# clock.net
KiCad netlist of a schematic drawn in EAGLE
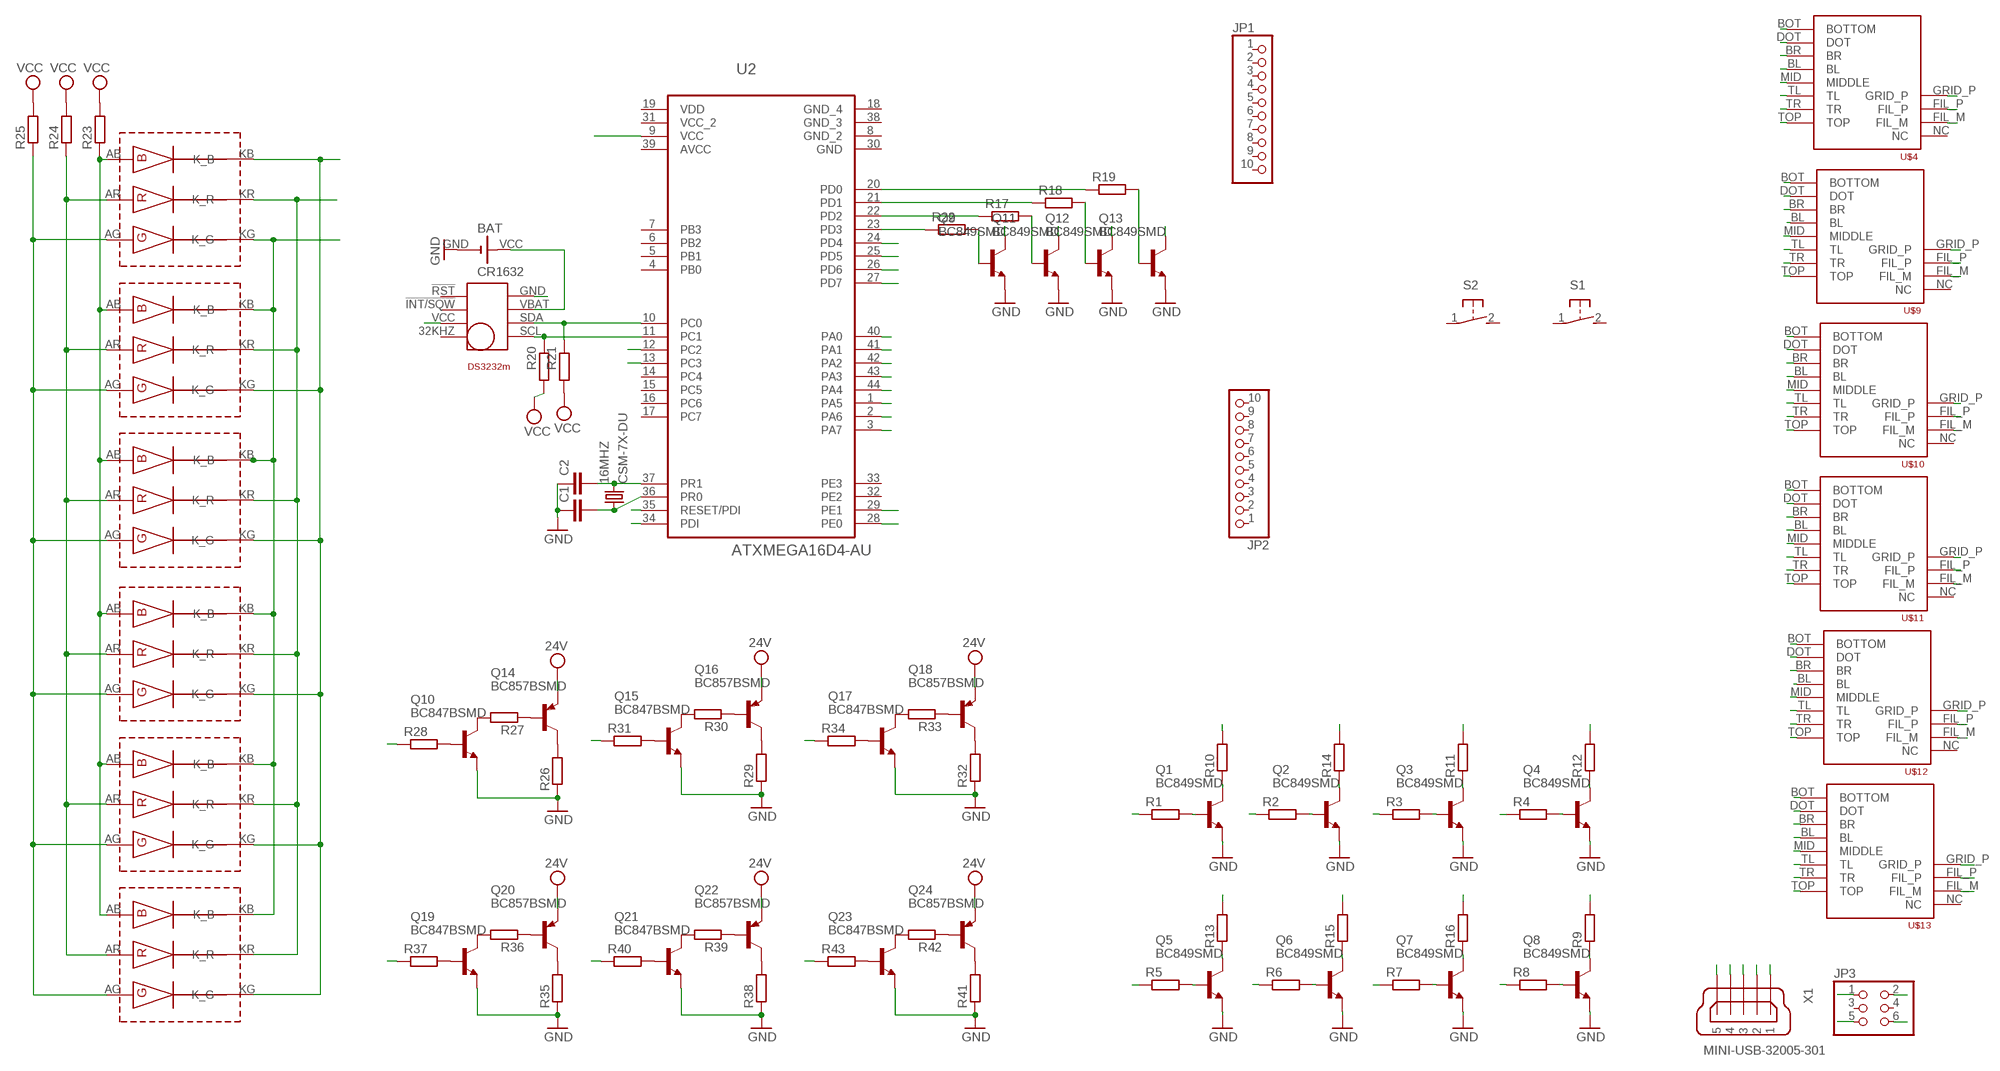
[diagram p0: schematic, sheet 1]

(export (version "E")
  (design (tool "Eeschema 10.0.6"))
  (components
    (comp (ref "16MHZ")
      (value "CSM-7X-DU")
      (footprint "eagle-import:CSM-7X-DU")
      (libsource (lib "eagle-import") (part "CSM-7X-DU"))
    )
    (comp (ref "BAT")
      (value "CR1632")
      (footprint "eagle-import:CR3232")
      (libsource (lib "eagle-import") (part "CR1632"))
    )
    (comp (ref "C1")
      (value "C-EUC0805K")
      (footprint "eagle-import:C0805K")
      (libsource (lib "eagle-import") (part "C-EUC0805K"))
    )
    (comp (ref "C2")
      (value "C-EUC0805K")
      (footprint "eagle-import:C0805K")
      (libsource (lib "eagle-import") (part "C-EUC0805K"))
    )
    (comp (ref "JP1")
      (value "PINHD-1X10")
      (footprint "eagle-import:1X10")
      (libsource (lib "eagle-import") (part "PINHD-1X10"))
    )
    (comp (ref "JP2")
      (value "PINHD-1X10")
      (footprint "eagle-import:1X10")
      (libsource (lib "eagle-import") (part "PINHD-1X10"))
    )
    (comp (ref "JP3")
      (value "PINHD-2X3/90")
      (footprint "eagle-import:2X03_90")
      (libsource (lib "eagle-import") (part "PINHD-2X3/90"))
    )
    (comp (ref "Q1")
      (value "BC849SMD")
      (footprint "eagle-import:SOT23-BEC")
      (libsource (lib "eagle-import") (part "BC849SMD"))
    )
    (comp (ref "Q2")
      (value "BC849SMD")
      (footprint "eagle-import:SOT23-BEC")
      (libsource (lib "eagle-import") (part "BC849SMD"))
    )
    (comp (ref "Q3")
      (value "BC849SMD")
      (footprint "eagle-import:SOT23-BEC")
      (libsource (lib "eagle-import") (part "BC849SMD"))
    )
    (comp (ref "Q4")
      (value "BC849SMD")
      (footprint "eagle-import:SOT23-BEC")
      (libsource (lib "eagle-import") (part "BC849SMD"))
    )
    (comp (ref "Q5")
      (value "BC849SMD")
      (footprint "eagle-import:SOT23-BEC")
      (libsource (lib "eagle-import") (part "BC849SMD"))
    )
    (comp (ref "Q6")
      (value "BC849SMD")
      (footprint "eagle-import:SOT23-BEC")
      (libsource (lib "eagle-import") (part "BC849SMD"))
    )
    (comp (ref "Q7")
      (value "BC849SMD")
      (footprint "eagle-import:SOT23-BEC")
      (libsource (lib "eagle-import") (part "BC849SMD"))
    )
    (comp (ref "Q8")
      (value "BC849SMD")
      (footprint "eagle-import:SOT23-BEC")
      (libsource (lib "eagle-import") (part "BC849SMD"))
    )
    (comp (ref "Q9")
      (value "BC849SMD")
      (footprint "eagle-import:SOT23-BEC")
      (libsource (lib "eagle-import") (part "BC849SMD"))
    )
    (comp (ref "Q10")
      (value "BC847BSMD")
      (footprint "eagle-import:SOT23")
      (libsource (lib "eagle-import") (part "BC847SMDB"))
    )
    (comp (ref "Q11")
      (value "BC849SMD")
      (footprint "eagle-import:SOT23-BEC")
      (libsource (lib "eagle-import") (part "BC849SMD"))
    )
    (comp (ref "Q12")
      (value "BC849SMD")
      (footprint "eagle-import:SOT23-BEC")
      (libsource (lib "eagle-import") (part "BC849SMD"))
    )
    (comp (ref "Q13")
      (value "BC849SMD")
      (footprint "eagle-import:SOT23-BEC")
      (libsource (lib "eagle-import") (part "BC849SMD"))
    )
    (comp (ref "Q14")
      (value "BC857BSMD")
      (footprint "eagle-import:SOT23-BEC")
      (libsource (lib "eagle-import") (part "BC857SMDB"))
    )
    (comp (ref "Q15")
      (value "BC847BSMD")
      (footprint "eagle-import:SOT23")
      (libsource (lib "eagle-import") (part "BC847SMDB"))
    )
    (comp (ref "Q16")
      (value "BC857BSMD")
      (footprint "eagle-import:SOT23-BEC")
      (libsource (lib "eagle-import") (part "BC857SMDB"))
    )
    (comp (ref "Q17")
      (value "BC847BSMD")
      (footprint "eagle-import:SOT23")
      (libsource (lib "eagle-import") (part "BC847SMDB"))
    )
    (comp (ref "Q18")
      (value "BC857BSMD")
      (footprint "eagle-import:SOT23-BEC")
      (libsource (lib "eagle-import") (part "BC857SMDB"))
    )
    (comp (ref "Q19")
      (value "BC847BSMD")
      (footprint "eagle-import:SOT23")
      (libsource (lib "eagle-import") (part "BC847SMDB"))
    )
    (comp (ref "Q20")
      (value "BC857BSMD")
      (footprint "eagle-import:SOT23-BEC")
      (libsource (lib "eagle-import") (part "BC857SMDB"))
    )
    (comp (ref "Q21")
      (value "BC847BSMD")
      (footprint "eagle-import:SOT23")
      (libsource (lib "eagle-import") (part "BC847SMDB"))
    )
    (comp (ref "Q22")
      (value "BC857BSMD")
      (footprint "eagle-import:SOT23-BEC")
      (libsource (lib "eagle-import") (part "BC857SMDB"))
    )
    (comp (ref "Q23")
      (value "BC847BSMD")
      (footprint "eagle-import:SOT23")
      (libsource (lib "eagle-import") (part "BC847SMDB"))
    )
    (comp (ref "Q24")
      (value "BC857BSMD")
      (footprint "eagle-import:SOT23-BEC")
      (libsource (lib "eagle-import") (part "BC857SMDB"))
    )
    (comp (ref "R1")
      (value "R-EU_0207/10")
      (footprint "eagle-import:0207_10")
      (libsource (lib "eagle-import") (part "R-EU_0207/10"))
    )
    (comp (ref "R2")
      (value "R-EU_0207/10")
      (footprint "eagle-import:0207_10")
      (libsource (lib "eagle-import") (part "R-EU_0207/10"))
    )
    (comp (ref "R3")
      (value "R-EU_0207/10")
      (footprint "eagle-import:0207_10")
      (libsource (lib "eagle-import") (part "R-EU_0207/10"))
    )
    (comp (ref "R4")
      (value "R-EU_0207/10")
      (footprint "eagle-import:0207_10")
      (libsource (lib "eagle-import") (part "R-EU_0207/10"))
    )
    (comp (ref "R5")
      (value "R-EU_0207/10")
      (footprint "eagle-import:0207_10")
      (libsource (lib "eagle-import") (part "R-EU_0207/10"))
    )
    (comp (ref "R6")
      (value "R-EU_0207/10")
      (footprint "eagle-import:0207_10")
      (libsource (lib "eagle-import") (part "R-EU_0207/10"))
    )
    (comp (ref "R7")
      (value "R-EU_0207/10")
      (footprint "eagle-import:0207_10")
      (libsource (lib "eagle-import") (part "R-EU_0207/10"))
    )
    (comp (ref "R8")
      (value "R-EU_0207/10")
      (footprint "eagle-import:0207_10")
      (libsource (lib "eagle-import") (part "R-EU_0207/10"))
    )
    (comp (ref "R9")
      (value "R-EU_0207/10")
      (footprint "eagle-import:0207_10")
      (libsource (lib "eagle-import") (part "R-EU_0207/10"))
    )
    (comp (ref "R10")
      (value "R-EU_0207/10")
      (footprint "eagle-import:0207_10")
      (libsource (lib "eagle-import") (part "R-EU_0207/10"))
    )
    (comp (ref "R11")
      (value "R-EU_0207/10")
      (footprint "eagle-import:0207_10")
      (libsource (lib "eagle-import") (part "R-EU_0207/10"))
    )
    (comp (ref "R12")
      (value "R-EU_0207/10")
      (footprint "eagle-import:0207_10")
      (libsource (lib "eagle-import") (part "R-EU_0207/10"))
    )
    (comp (ref "R13")
      (value "R-EU_0207/10")
      (footprint "eagle-import:0207_10")
      (libsource (lib "eagle-import") (part "R-EU_0207/10"))
    )
    (comp (ref "R14")
      (value "R-EU_0207/10")
      (footprint "eagle-import:0207_10")
      (libsource (lib "eagle-import") (part "R-EU_0207/10"))
    )
    (comp (ref "R15")
      (value "R-EU_0207/10")
      (footprint "eagle-import:0207_10")
      (libsource (lib "eagle-import") (part "R-EU_0207/10"))
    )
    (comp (ref "R16")
      (value "R-EU_0207/10")
      (footprint "eagle-import:0207_10")
      (libsource (lib "eagle-import") (part "R-EU_0207/10"))
    )
    (comp (ref "R17")
      (value "R-EU_0207/10")
      (footprint "eagle-import:0207_10")
      (libsource (lib "eagle-import") (part "R-EU_0207/10"))
    )
    (comp (ref "R18")
      (value "R-EU_0207/10")
      (footprint "eagle-import:0207_10")
      (libsource (lib "eagle-import") (part "R-EU_0207/10"))
    )
    (comp (ref "R19")
      (value "R-EU_0207/10")
      (footprint "eagle-import:0207_10")
      (libsource (lib "eagle-import") (part "R-EU_0207/10"))
    )
    (comp (ref "R20")
      (value "R-EU_0207/10")
      (footprint "eagle-import:0207_10")
      (libsource (lib "eagle-import") (part "R-EU_0207/10"))
    )
    (comp (ref "R21")
      (value "R-EU_0207/10")
      (footprint "eagle-import:0207_10")
      (libsource (lib "eagle-import") (part "R-EU_0207/10"))
    )
    (comp (ref "R22")
      (value "R-EU_0207/10")
      (footprint "eagle-import:0207_10")
      (libsource (lib "eagle-import") (part "R-EU_0207/10"))
    )
    (comp (ref "R23")
      (value "R-EU_0207/10")
      (footprint "eagle-import:0207_10")
      (libsource (lib "eagle-import") (part "R-EU_0207/10"))
    )
    (comp (ref "R24")
      (value "R-EU_0207/10")
      (footprint "eagle-import:0207_10")
      (libsource (lib "eagle-import") (part "R-EU_0207/10"))
    )
    (comp (ref "R25")
      (value "R-EU_0207/10")
      (footprint "eagle-import:0207_10")
      (libsource (lib "eagle-import") (part "R-EU_0207/10"))
    )
    (comp (ref "R26")
      (value "R-EU_0207/10")
      (footprint "eagle-import:0207_10")
      (libsource (lib "eagle-import") (part "R-EU_0207/10"))
    )
    (comp (ref "R27")
      (value "R-EU_0207/10")
      (footprint "eagle-import:0207_10")
      (libsource (lib "eagle-import") (part "R-EU_0207/10"))
    )
    (comp (ref "R28")
      (value "R-EU_0207/10")
      (footprint "eagle-import:0207_10")
      (libsource (lib "eagle-import") (part "R-EU_0207/10"))
    )
    (comp (ref "R29")
      (value "R-EU_0207/10")
      (footprint "eagle-import:0207_10")
      (libsource (lib "eagle-import") (part "R-EU_0207/10"))
    )
    (comp (ref "R30")
      (value "R-EU_0207/10")
      (footprint "eagle-import:0207_10")
      (libsource (lib "eagle-import") (part "R-EU_0207/10"))
    )
    (comp (ref "R31")
      (value "R-EU_0207/10")
      (footprint "eagle-import:0207_10")
      (libsource (lib "eagle-import") (part "R-EU_0207/10"))
    )
    (comp (ref "R32")
      (value "R-EU_0207/10")
      (footprint "eagle-import:0207_10")
      (libsource (lib "eagle-import") (part "R-EU_0207/10"))
    )
    (comp (ref "R33")
      (value "R-EU_0207/10")
      (footprint "eagle-import:0207_10")
      (libsource (lib "eagle-import") (part "R-EU_0207/10"))
    )
    (comp (ref "R34")
      (value "R-EU_0207/10")
      (footprint "eagle-import:0207_10")
      (libsource (lib "eagle-import") (part "R-EU_0207/10"))
    )
    (comp (ref "R35")
      (value "R-EU_0207/10")
      (footprint "eagle-import:0207_10")
      (libsource (lib "eagle-import") (part "R-EU_0207/10"))
    )
    (comp (ref "R36")
      (value "R-EU_0207/10")
      (footprint "eagle-import:0207_10")
      (libsource (lib "eagle-import") (part "R-EU_0207/10"))
    )
    (comp (ref "R37")
      (value "R-EU_0207/10")
      (footprint "eagle-import:0207_10")
      (libsource (lib "eagle-import") (part "R-EU_0207/10"))
    )
    (comp (ref "R38")
      (value "R-EU_0207/10")
      (footprint "eagle-import:0207_10")
      (libsource (lib "eagle-import") (part "R-EU_0207/10"))
    )
    (comp (ref "R39")
      (value "R-EU_0207/10")
      (footprint "eagle-import:0207_10")
      (libsource (lib "eagle-import") (part "R-EU_0207/10"))
    )
    (comp (ref "R40")
      (value "R-EU_0207/10")
      (footprint "eagle-import:0207_10")
      (libsource (lib "eagle-import") (part "R-EU_0207/10"))
    )
    (comp (ref "R41")
      (value "R-EU_0207/10")
      (footprint "eagle-import:0207_10")
      (libsource (lib "eagle-import") (part "R-EU_0207/10"))
    )
    (comp (ref "R42")
      (value "R-EU_0207/10")
      (footprint "eagle-import:0207_10")
      (libsource (lib "eagle-import") (part "R-EU_0207/10"))
    )
    (comp (ref "R43")
      (value "R-EU_0207/10")
      (footprint "eagle-import:0207_10")
      (libsource (lib "eagle-import") (part "R-EU_0207/10"))
    )
    (comp (ref "S1")
      (value "31-XX")
      (footprint "eagle-import:B3F-31XX")
      (fields (field (name "MPN") "B3F-3100"))
      (libsource (lib "eagle-import") (part "31-XX"))
    )
    (comp (ref "S2")
      (value "31-XX")
      (footprint "eagle-import:B3F-31XX")
      (fields (field (name "MPN") "B3F-3100"))
      (libsource (lib "eagle-import") (part "31-XX"))
    )
    (comp (ref "U$1")
      (value "RGB-SMT-SQUARE5X5MM")
      (footprint "eagle-import:SMT-SQUARE5")
      (libsource (lib "eagle-import") (part "RGB-SMT-SQUARE5X5MM"))
    )
    (comp (ref "U$2")
      (value "DS3232M")
      (footprint "eagle-import:SOIC8")
      (libsource (lib "eagle-import") (part "DS3232M"))
    )
    (comp (ref "U$3")
      (value "RGB-SMT-SQUARE5X5MM")
      (footprint "eagle-import:SMT-SQUARE5")
      (libsource (lib "eagle-import") (part "RGB-SMT-SQUARE5X5MM"))
    )
    (comp (ref "U$4")
      (value "IV6_NUMITRONLARGE")
      (footprint "eagle-import:IV6_NUMITRON_PAC_LARGE")
      (libsource (lib "eagle-import") (part "IV6_NUMITRONLARGE"))
    )
    (comp (ref "U$5")
      (value "RGB-SMT-SQUARE5X5MM")
      (footprint "eagle-import:SMT-SQUARE5")
      (libsource (lib "eagle-import") (part "RGB-SMT-SQUARE5X5MM"))
    )
    (comp (ref "U$6")
      (value "RGB-SMT-SQUARE5X5MM")
      (footprint "eagle-import:SMT-SQUARE5")
      (libsource (lib "eagle-import") (part "RGB-SMT-SQUARE5X5MM"))
    )
    (comp (ref "U$7")
      (value "RGB-SMT-SQUARE5X5MM")
      (footprint "eagle-import:SMT-SQUARE5")
      (libsource (lib "eagle-import") (part "RGB-SMT-SQUARE5X5MM"))
    )
    (comp (ref "U$8")
      (value "RGB-SMT-SQUARE5X5MM")
      (footprint "eagle-import:SMT-SQUARE5")
      (libsource (lib "eagle-import") (part "RGB-SMT-SQUARE5X5MM"))
    )
    (comp (ref "U$9")
      (value "IV6_NUMITRONLARGE")
      (footprint "eagle-import:IV6_NUMITRON_PAC_LARGE")
      (libsource (lib "eagle-import") (part "IV6_NUMITRONLARGE"))
    )
    (comp (ref "U$10")
      (value "IV6_NUMITRONLARGE")
      (footprint "eagle-import:IV6_NUMITRON_PAC_LARGE")
      (libsource (lib "eagle-import") (part "IV6_NUMITRONLARGE"))
    )
    (comp (ref "U$11")
      (value "IV6_NUMITRONLARGE")
      (footprint "eagle-import:IV6_NUMITRON_PAC_LARGE")
      (libsource (lib "eagle-import") (part "IV6_NUMITRONLARGE"))
    )
    (comp (ref "U$12")
      (value "IV6_NUMITRONLARGE")
      (footprint "eagle-import:IV6_NUMITRON_PAC_LARGE")
      (libsource (lib "eagle-import") (part "IV6_NUMITRONLARGE"))
    )
    (comp (ref "U$13")
      (value "IV6_NUMITRONLARGE")
      (footprint "eagle-import:IV6_NUMITRON_PAC_LARGE")
      (libsource (lib "eagle-import") (part "IV6_NUMITRONLARGE"))
    )
    (comp (ref "U2")
      (value "ATXMEGA16D4-AU")
      (footprint "eagle-import:QFP80P1200X1200X120-44N")
      (libsource (lib "eagle-import") (part "ATXMEGA16D4-AU"))
    )
    (comp (ref "X1")
      (value "MINI-USB-32005-301")
      (footprint "eagle-import:32005-301")
      (libsource (lib "eagle-import") (part "MINI-USB-32005-301"))
    )
  )
  (nets
    (net (code "1") (name "/AVCC") (class "Default")
      (node (ref "U2") (pin "39") (pinfunction "AVCC_39") (pintype "power_in"))
    )
    (net (code "2") (name "/B") (class "Default")
      (node (ref "Q11") (pin "C") (pinfunction "C_C") (pintype "passive"))
      (node (ref "U$1") (pin "KB") (pinfunction "K_B_KB") (pintype "bidirectional"))
      (node (ref "U$3") (pin "KG") (pinfunction "K_G_KG") (pintype "bidirectional"))
      (node (ref "U$5") (pin "KG") (pinfunction "K_G_KG") (pintype "bidirectional"))
      (node (ref "U$6") (pin "KG") (pinfunction "K_G_KG") (pintype "bidirectional"))
      (node (ref "U$7") (pin "KG") (pinfunction "K_G_KG") (pintype "bidirectional"))
      (node (ref "U$8") (pin "KG") (pinfunction "K_G_KG") (pintype "bidirectional"))
    )
    (net (code "3") (name "/BL") (class "Default")
      (node (ref "U$10") (pin "BL") (pinfunction "BL_BL") (pintype "bidirectional"))
      (node (ref "U$11") (pin "BL") (pinfunction "BL_BL") (pintype "bidirectional"))
      (node (ref "U$12") (pin "BL") (pinfunction "BL_BL") (pintype "bidirectional"))
      (node (ref "U$13") (pin "BL") (pinfunction "BL_BL") (pintype "bidirectional"))
      (node (ref "U$4") (pin "BL") (pinfunction "BL_BL") (pintype "bidirectional"))
      (node (ref "U$9") (pin "BL") (pinfunction "BL_BL") (pintype "bidirectional"))
    )
    (net (code "4") (name "/BOT") (class "Default")
      (node (ref "U$10") (pin "BOT") (pinfunction "BOTTOM_BOT") (pintype "bidirectional"))
      (node (ref "U$11") (pin "BOT") (pinfunction "BOTTOM_BOT") (pintype "bidirectional"))
      (node (ref "U$12") (pin "BOT") (pinfunction "BOTTOM_BOT") (pintype "bidirectional"))
      (node (ref "U$13") (pin "BOT") (pinfunction "BOTTOM_BOT") (pintype "bidirectional"))
      (node (ref "U$4") (pin "BOT") (pinfunction "BOTTOM_BOT") (pintype "bidirectional"))
      (node (ref "U$9") (pin "BOT") (pinfunction "BOTTOM_BOT") (pintype "bidirectional"))
    )
    (net (code "5") (name "/BR") (class "Default")
      (node (ref "U$10") (pin "BR") (pinfunction "BR_BR") (pintype "bidirectional"))
      (node (ref "U$11") (pin "BR") (pinfunction "BR_BR") (pintype "bidirectional"))
      (node (ref "U$12") (pin "BR") (pinfunction "BR_BR") (pintype "bidirectional"))
      (node (ref "U$13") (pin "BR") (pinfunction "BR_BR") (pintype "bidirectional"))
      (node (ref "U$4") (pin "BR") (pinfunction "BR_BR") (pintype "bidirectional"))
      (node (ref "U$9") (pin "BR") (pinfunction "BR_BR") (pintype "bidirectional"))
    )
    (net (code "6") (name "/DOT") (class "Default")
      (node (ref "U$10") (pin "DOT") (pinfunction "DOT_DOT") (pintype "bidirectional"))
      (node (ref "U$11") (pin "DOT") (pinfunction "DOT_DOT") (pintype "bidirectional"))
      (node (ref "U$12") (pin "DOT") (pinfunction "DOT_DOT") (pintype "bidirectional"))
      (node (ref "U$13") (pin "DOT") (pinfunction "DOT_DOT") (pintype "bidirectional"))
      (node (ref "U$4") (pin "DOT") (pinfunction "DOT_DOT") (pintype "bidirectional"))
      (node (ref "U$9") (pin "DOT") (pinfunction "DOT_DOT") (pintype "bidirectional"))
    )
    (net (code "7") (name "/FIL_P") (class "Default")
      (node (ref "U$10") (pin "FIL_P") (pinfunction "FIL_P_FIL_P") (pintype "bidirectional"))
      (node (ref "U$11") (pin "FIL_P") (pinfunction "FIL_P_FIL_P") (pintype "bidirectional"))
      (node (ref "U$12") (pin "FIL_P") (pinfunction "FIL_P_FIL_P") (pintype "bidirectional"))
      (node (ref "U$13") (pin "FIL_P") (pinfunction "FIL_P_FIL_P") (pintype "bidirectional"))
      (node (ref "U$4") (pin "FIL_P") (pinfunction "FIL_P_FIL_P") (pintype "bidirectional"))
      (node (ref "U$9") (pin "FIL_P") (pinfunction "FIL_P_FIL_P") (pintype "bidirectional"))
    )
    (net (code "8") (name "/G") (class "Default")
      (node (ref "Q12") (pin "C") (pinfunction "C_C") (pintype "passive"))
      (node (ref "U$1") (pin "KG") (pinfunction "K_G_KG") (pintype "bidirectional"))
      (node (ref "U$3") (pin "KB") (pinfunction "K_B_KB") (pintype "bidirectional"))
      (node (ref "U$5") (pin "KB") (pinfunction "K_B_KB") (pintype "bidirectional"))
      (node (ref "U$6") (pin "KB") (pinfunction "K_B_KB") (pintype "bidirectional"))
      (node (ref "U$7") (pin "KB") (pinfunction "K_B_KB") (pintype "bidirectional"))
      (node (ref "U$8") (pin "KB") (pinfunction "K_B_KB") (pintype "bidirectional"))
    )
    (net (code "9") (name "/MID") (class "Default")
      (node (ref "U$10") (pin "MID") (pinfunction "MIDDLE_MID") (pintype "bidirectional"))
      (node (ref "U$11") (pin "MID") (pinfunction "MIDDLE_MID") (pintype "bidirectional"))
      (node (ref "U$12") (pin "MID") (pinfunction "MIDDLE_MID") (pintype "bidirectional"))
      (node (ref "U$13") (pin "MID") (pinfunction "MIDDLE_MID") (pintype "bidirectional"))
      (node (ref "U$4") (pin "MID") (pinfunction "MIDDLE_MID") (pintype "bidirectional"))
      (node (ref "U$9") (pin "MID") (pinfunction "MIDDLE_MID") (pintype "bidirectional"))
    )
    (net (code "10") (name "/PA0") (class "Default")
      (node (ref "R1") (pin "1") (pinfunction "1_1") (pintype "passive"))
      (node (ref "U2") (pin "40") (pinfunction "PA0_40") (pintype "bidirectional"))
    )
    (net (code "11") (name "/PA1") (class "Default")
      (node (ref "R2") (pin "1") (pinfunction "1_1") (pintype "passive"))
      (node (ref "U2") (pin "41") (pinfunction "PA1_41") (pintype "bidirectional"))
    )
    (net (code "12") (name "/PA2") (class "Default")
      (node (ref "R3") (pin "1") (pinfunction "1_1") (pintype "passive"))
      (node (ref "U2") (pin "42") (pinfunction "PA2_42") (pintype "bidirectional"))
    )
    (net (code "13") (name "/PA3") (class "Default")
      (node (ref "R4") (pin "1") (pinfunction "1_1") (pintype "passive"))
      (node (ref "U2") (pin "43") (pinfunction "PA3_43") (pintype "bidirectional"))
    )
    (net (code "14") (name "/PA4") (class "Default")
      (node (ref "R5") (pin "1") (pinfunction "1_1") (pintype "passive"))
      (node (ref "U2") (pin "44") (pinfunction "PA4_44") (pintype "bidirectional"))
    )
    (net (code "15") (name "/PA5") (class "Default")
      (node (ref "R6") (pin "1") (pinfunction "1_1") (pintype "passive"))
      (node (ref "U2") (pin "1") (pinfunction "PA5_1") (pintype "bidirectional"))
    )
    (net (code "16") (name "/PA6") (class "Default")
      (node (ref "R7") (pin "1") (pinfunction "1_1") (pintype "passive"))
      (node (ref "U2") (pin "2") (pinfunction "PA6_2") (pintype "bidirectional"))
    )
    (net (code "17") (name "/PA7") (class "Default")
      (node (ref "R8") (pin "1") (pinfunction "1_1") (pintype "passive"))
      (node (ref "U2") (pin "3") (pinfunction "PA7_3") (pintype "bidirectional"))
    )
    (net (code "18") (name "/PD4") (class "Default")
      (node (ref "R28") (pin "1") (pinfunction "1_1") (pintype "passive"))
      (node (ref "U2") (pin "24") (pinfunction "PD4_24") (pintype "bidirectional"))
    )
    (net (code "19") (name "/PD5") (class "Default")
      (node (ref "R31") (pin "1") (pinfunction "1_1") (pintype "passive"))
      (node (ref "U2") (pin "25") (pinfunction "PD5_25") (pintype "bidirectional"))
    )
    (net (code "20") (name "/PD6") (class "Default")
      (node (ref "R34") (pin "1") (pinfunction "1_1") (pintype "passive"))
      (node (ref "U2") (pin "26") (pinfunction "PD6_26") (pintype "bidirectional"))
    )
    (net (code "21") (name "/PD7") (class "Default")
      (node (ref "R37") (pin "1") (pinfunction "1_1") (pintype "passive"))
      (node (ref "U2") (pin "27") (pinfunction "PD7_27") (pintype "bidirectional"))
    )
    (net (code "22") (name "/PDI") (class "Default")
      (node (ref "JP3") (pin "1") (pinfunction "1_1") (pintype "passive"))
      (node (ref "U2") (pin "34") (pinfunction "PDI_34") (pintype "passive"))
    )
    (net (code "23") (name "/PE0") (class "Default")
      (node (ref "R40") (pin "1") (pinfunction "1_1") (pintype "passive"))
      (node (ref "U2") (pin "28") (pinfunction "PE0_28") (pintype "bidirectional"))
    )
    (net (code "24") (name "/PE1") (class "Default")
      (node (ref "R43") (pin "1") (pinfunction "1_1") (pintype "passive"))
      (node (ref "U2") (pin "29") (pinfunction "PE1_29") (pintype "bidirectional"))
    )
    (net (code "25") (name "/R") (class "Default")
      (node (ref "Q13") (pin "C") (pinfunction "C_C") (pintype "passive"))
      (node (ref "U$1") (pin "KR") (pinfunction "K_R_KR") (pintype "bidirectional"))
      (node (ref "U$3") (pin "KR") (pinfunction "K_R_KR") (pintype "bidirectional"))
      (node (ref "U$5") (pin "KR") (pinfunction "K_R_KR") (pintype "bidirectional"))
      (node (ref "U$6") (pin "KR") (pinfunction "K_R_KR") (pintype "bidirectional"))
      (node (ref "U$7") (pin "KR") (pinfunction "K_R_KR") (pintype "bidirectional"))
      (node (ref "U$8") (pin "KR") (pinfunction "K_R_KR") (pintype "bidirectional"))
    )
    (net (code "26") (name "/RESET") (class "Default")
      (node (ref "JP3") (pin "5") (pinfunction "5_5") (pintype "passive"))
      (node (ref "U2") (pin "35") (pinfunction "RESET/PDI_35") (pintype "input"))
    )
    (net (code "27") (name "/RX") (class "Default")
      (node (ref "U2") (pin "12") (pinfunction "PC2_12") (pintype "bidirectional"))
      (node (ref "X1") (pin "4") (pinfunction "4_4") (pintype "passive"))
    )
    (net (code "28") (name "/TL") (class "Default")
      (node (ref "U$10") (pin "TL") (pinfunction "TL_TL") (pintype "bidirectional"))
      (node (ref "U$11") (pin "TL") (pinfunction "TL_TL") (pintype "bidirectional"))
      (node (ref "U$12") (pin "TL") (pinfunction "TL_TL") (pintype "bidirectional"))
      (node (ref "U$13") (pin "TL") (pinfunction "TL_TL") (pintype "bidirectional"))
      (node (ref "U$4") (pin "TL") (pinfunction "TL_TL") (pintype "bidirectional"))
      (node (ref "U$9") (pin "TL") (pinfunction "TL_TL") (pintype "bidirectional"))
    )
    (net (code "29") (name "/TOP") (class "Default")
      (node (ref "U$10") (pin "TOP") (pinfunction "TOP_TOP") (pintype "bidirectional"))
      (node (ref "U$11") (pin "TOP") (pinfunction "TOP_TOP") (pintype "bidirectional"))
      (node (ref "U$12") (pin "TOP") (pinfunction "TOP_TOP") (pintype "bidirectional"))
      (node (ref "U$13") (pin "TOP") (pinfunction "TOP_TOP") (pintype "bidirectional"))
      (node (ref "U$4") (pin "TOP") (pinfunction "TOP_TOP") (pintype "bidirectional"))
      (node (ref "U$9") (pin "TOP") (pinfunction "TOP_TOP") (pintype "bidirectional"))
    )
    (net (code "30") (name "/TR") (class "Default")
      (node (ref "U$10") (pin "TR") (pinfunction "TR_TR") (pintype "bidirectional"))
      (node (ref "U$11") (pin "TR") (pinfunction "TR_TR") (pintype "bidirectional"))
      (node (ref "U$12") (pin "TR") (pinfunction "TR_TR") (pintype "bidirectional"))
      (node (ref "U$13") (pin "TR") (pinfunction "TR_TR") (pintype "bidirectional"))
      (node (ref "U$4") (pin "TR") (pinfunction "TR_TR") (pintype "bidirectional"))
      (node (ref "U$9") (pin "TR") (pinfunction "TR_TR") (pintype "bidirectional"))
    )
    (net (code "31") (name "/TX") (class "Default")
      (node (ref "U2") (pin "13") (pinfunction "PC3_13") (pintype "bidirectional"))
      (node (ref "X1") (pin "3") (pinfunction "3_3") (pintype "passive"))
    )
    (net (code "32") (name "/VCC_2") (class "Default")
      (node (ref "U2") (pin "31") (pinfunction "VCC_2_31") (pintype "power_in"))
    )
    (net (code "33") (name "/VDD") (class "Default")
      (node (ref "U2") (pin "19") (pinfunction "VDD_19") (pintype "power_in"))
    )
    (net (code "34") (name "24V") (class "Default")
      (node (ref "Q14") (pin "E") (pinfunction "E_E") (pintype "passive"))
      (node (ref "Q16") (pin "E") (pinfunction "E_E") (pintype "passive"))
      (node (ref "Q18") (pin "E") (pinfunction "E_E") (pintype "passive"))
      (node (ref "Q20") (pin "E") (pinfunction "E_E") (pintype "passive"))
      (node (ref "Q22") (pin "E") (pinfunction "E_E") (pintype "passive"))
      (node (ref "Q24") (pin "E") (pinfunction "E_E") (pintype "passive"))
    )
    (net (code "35") (name "GND") (class "Default")
      (node (ref "BAT") (pin "GND") (pinfunction "-_GND") (pintype "passive"))
      (node (ref "C1") (pin "1") (pinfunction "1_1") (pintype "passive"))
      (node (ref "C2") (pin "1") (pinfunction "1_1") (pintype "passive"))
      (node (ref "JP3") (pin "6") (pinfunction "6_6") (pintype "passive"))
      (node (ref "Q1") (pin "E") (pinfunction "E_E") (pintype "passive"))
      (node (ref "Q10") (pin "2") (pinfunction "E_2") (pintype "passive"))
      (node (ref "Q11") (pin "E") (pinfunction "E_E") (pintype "passive"))
      (node (ref "Q12") (pin "E") (pinfunction "E_E") (pintype "passive"))
      (node (ref "Q13") (pin "E") (pinfunction "E_E") (pintype "passive"))
      (node (ref "Q15") (pin "2") (pinfunction "E_2") (pintype "passive"))
      (node (ref "Q17") (pin "2") (pinfunction "E_2") (pintype "passive"))
      (node (ref "Q19") (pin "2") (pinfunction "E_2") (pintype "passive"))
      (node (ref "Q2") (pin "E") (pinfunction "E_E") (pintype "passive"))
      (node (ref "Q21") (pin "2") (pinfunction "E_2") (pintype "passive"))
      (node (ref "Q23") (pin "2") (pinfunction "E_2") (pintype "passive"))
      (node (ref "Q3") (pin "E") (pinfunction "E_E") (pintype "passive"))
      (node (ref "Q4") (pin "E") (pinfunction "E_E") (pintype "passive"))
      (node (ref "Q5") (pin "E") (pinfunction "E_E") (pintype "passive"))
      (node (ref "Q6") (pin "E") (pinfunction "E_E") (pintype "passive"))
      (node (ref "Q7") (pin "E") (pinfunction "E_E") (pintype "passive"))
      (node (ref "Q8") (pin "E") (pinfunction "E_E") (pintype "passive"))
      (node (ref "Q9") (pin "E") (pinfunction "E_E") (pintype "passive"))
      (node (ref "R26") (pin "1") (pinfunction "1_1") (pintype "passive"))
      (node (ref "R29") (pin "1") (pinfunction "1_1") (pintype "passive"))
      (node (ref "R32") (pin "1") (pinfunction "1_1") (pintype "passive"))
      (node (ref "R35") (pin "1") (pinfunction "1_1") (pintype "passive"))
      (node (ref "R38") (pin "1") (pinfunction "1_1") (pintype "passive"))
      (node (ref "R41") (pin "1") (pinfunction "1_1") (pintype "passive"))
      (node (ref "U$2") (pin "GND") (pinfunction "GND_GND") (pintype "power_in"))
      (node (ref "X1") (pin "1") (pinfunction "1_1") (pintype "passive"))
      (node (ref "X1") (pin "2") (pinfunction "2_2") (pintype "passive"))
    )
    (net (code "36") (name "Net-(BAT-+)") (class "Default")
      (node (ref "BAT") (pin "VCC") (pinfunction "+_VCC") (pintype "passive"))
      (node (ref "U$2") (pin "VBAT") (pinfunction "VBAT_VBAT") (pintype "power_in"))
    )
    (net (code "37") (name "Net-(Q1-PadB)") (class "Default")
      (node (ref "Q1") (pin "B") (pinfunction "B_B") (pintype "passive"))
      (node (ref "R1") (pin "2") (pinfunction "2_2") (pintype "passive"))
    )
    (net (code "38") (name "Net-(Q1-PadC)") (class "Default")
      (node (ref "Q1") (pin "C") (pinfunction "C_C") (pintype "passive"))
      (node (ref "R10") (pin "1") (pinfunction "1_1") (pintype "passive"))
    )
    (net (code "39") (name "Net-(Q2-PadB)") (class "Default")
      (node (ref "Q2") (pin "B") (pinfunction "B_B") (pintype "passive"))
      (node (ref "R2") (pin "2") (pinfunction "2_2") (pintype "passive"))
    )
    (net (code "40") (name "Net-(Q2-PadC)") (class "Default")
      (node (ref "Q2") (pin "C") (pinfunction "C_C") (pintype "passive"))
      (node (ref "R14") (pin "1") (pinfunction "1_1") (pintype "passive"))
    )
    (net (code "41") (name "Net-(Q3-PadB)") (class "Default")
      (node (ref "Q3") (pin "B") (pinfunction "B_B") (pintype "passive"))
      (node (ref "R3") (pin "2") (pinfunction "2_2") (pintype "passive"))
    )
    (net (code "42") (name "Net-(Q3-PadC)") (class "Default")
      (node (ref "Q3") (pin "C") (pinfunction "C_C") (pintype "passive"))
      (node (ref "R11") (pin "1") (pinfunction "1_1") (pintype "passive"))
    )
    (net (code "43") (name "Net-(Q4-PadB)") (class "Default")
      (node (ref "Q4") (pin "B") (pinfunction "B_B") (pintype "passive"))
      (node (ref "R4") (pin "2") (pinfunction "2_2") (pintype "passive"))
    )
    (net (code "44") (name "Net-(Q4-PadC)") (class "Default")
      (node (ref "Q4") (pin "C") (pinfunction "C_C") (pintype "passive"))
      (node (ref "R12") (pin "1") (pinfunction "1_1") (pintype "passive"))
    )
    (net (code "45") (name "Net-(Q5-PadB)") (class "Default")
      (node (ref "Q5") (pin "B") (pinfunction "B_B") (pintype "passive"))
      (node (ref "R5") (pin "2") (pinfunction "2_2") (pintype "passive"))
    )
    (net (code "46") (name "Net-(Q5-PadC)") (class "Default")
      (node (ref "Q5") (pin "C") (pinfunction "C_C") (pintype "passive"))
      (node (ref "R13") (pin "1") (pinfunction "1_1") (pintype "passive"))
    )
    (net (code "47") (name "Net-(Q6-PadB)") (class "Default")
      (node (ref "Q6") (pin "B") (pinfunction "B_B") (pintype "passive"))
      (node (ref "R6") (pin "2") (pinfunction "2_2") (pintype "passive"))
    )
    (net (code "48") (name "Net-(Q6-PadC)") (class "Default")
      (node (ref "Q6") (pin "C") (pinfunction "C_C") (pintype "passive"))
      (node (ref "R15") (pin "1") (pinfunction "1_1") (pintype "passive"))
    )
    (net (code "49") (name "Net-(Q7-PadB)") (class "Default")
      (node (ref "Q7") (pin "B") (pinfunction "B_B") (pintype "passive"))
      (node (ref "R7") (pin "2") (pinfunction "2_2") (pintype "passive"))
    )
    (net (code "50") (name "Net-(Q7-PadC)") (class "Default")
      (node (ref "Q7") (pin "C") (pinfunction "C_C") (pintype "passive"))
      (node (ref "R16") (pin "1") (pinfunction "1_1") (pintype "passive"))
    )
    (net (code "51") (name "Net-(Q8-PadB)") (class "Default")
      (node (ref "Q8") (pin "B") (pinfunction "B_B") (pintype "passive"))
      (node (ref "R8") (pin "2") (pinfunction "2_2") (pintype "passive"))
    )
    (net (code "52") (name "Net-(Q8-PadC)") (class "Default")
      (node (ref "Q8") (pin "C") (pinfunction "C_C") (pintype "passive"))
      (node (ref "R9") (pin "1") (pinfunction "1_1") (pintype "passive"))
    )
    (net (code "53") (name "Net-(Q9-PadB)") (class "Default")
      (node (ref "Q9") (pin "B") (pinfunction "B_B") (pintype "passive"))
      (node (ref "R22") (pin "2") (pinfunction "2_2") (pintype "passive"))
    )
    (net (code "54") (name "Net-(Q10-B)") (class "Default")
      (node (ref "Q10") (pin "1") (pinfunction "B_1") (pintype "passive"))
      (node (ref "R28") (pin "2") (pinfunction "2_2") (pintype "passive"))
    )
    (net (code "55") (name "Net-(Q10-C)") (class "Default")
      (node (ref "Q10") (pin "3") (pinfunction "C_3") (pintype "passive"))
      (node (ref "R27") (pin "2") (pinfunction "2_2") (pintype "passive"))
    )
    (net (code "56") (name "Net-(Q11-PadB)") (class "Default")
      (node (ref "Q11") (pin "B") (pinfunction "B_B") (pintype "passive"))
      (node (ref "R17") (pin "2") (pinfunction "2_2") (pintype "passive"))
    )
    (net (code "57") (name "Net-(Q12-PadB)") (class "Default")
      (node (ref "Q12") (pin "B") (pinfunction "B_B") (pintype "passive"))
      (node (ref "R18") (pin "2") (pinfunction "2_2") (pintype "passive"))
    )
    (net (code "58") (name "Net-(Q13-PadB)") (class "Default")
      (node (ref "Q13") (pin "B") (pinfunction "B_B") (pintype "passive"))
      (node (ref "R19") (pin "2") (pinfunction "2_2") (pintype "passive"))
    )
    (net (code "59") (name "Net-(Q14-PadB)") (class "Default")
      (node (ref "Q14") (pin "B") (pinfunction "B_B") (pintype "passive"))
      (node (ref "R27") (pin "1") (pinfunction "1_1") (pintype "passive"))
    )
    (net (code "60") (name "Net-(Q14-PadC)") (class "Default")
      (node (ref "Q14") (pin "C") (pinfunction "C_C") (pintype "passive"))
      (node (ref "R26") (pin "2") (pinfunction "2_2") (pintype "passive"))
    )
    (net (code "61") (name "Net-(Q15-B)") (class "Default")
      (node (ref "Q15") (pin "1") (pinfunction "B_1") (pintype "passive"))
      (node (ref "R31") (pin "2") (pinfunction "2_2") (pintype "passive"))
    )
    (net (code "62") (name "Net-(Q15-C)") (class "Default")
      (node (ref "Q15") (pin "3") (pinfunction "C_3") (pintype "passive"))
      (node (ref "R30") (pin "2") (pinfunction "2_2") (pintype "passive"))
    )
    (net (code "63") (name "Net-(Q16-PadB)") (class "Default")
      (node (ref "Q16") (pin "B") (pinfunction "B_B") (pintype "passive"))
      (node (ref "R30") (pin "1") (pinfunction "1_1") (pintype "passive"))
    )
    (net (code "64") (name "Net-(Q16-PadC)") (class "Default")
      (node (ref "Q16") (pin "C") (pinfunction "C_C") (pintype "passive"))
      (node (ref "R29") (pin "2") (pinfunction "2_2") (pintype "passive"))
    )
    (net (code "65") (name "Net-(Q17-B)") (class "Default")
      (node (ref "Q17") (pin "1") (pinfunction "B_1") (pintype "passive"))
      (node (ref "R34") (pin "2") (pinfunction "2_2") (pintype "passive"))
    )
    (net (code "66") (name "Net-(Q17-C)") (class "Default")
      (node (ref "Q17") (pin "3") (pinfunction "C_3") (pintype "passive"))
      (node (ref "R33") (pin "2") (pinfunction "2_2") (pintype "passive"))
    )
    (net (code "67") (name "Net-(Q18-PadB)") (class "Default")
      (node (ref "Q18") (pin "B") (pinfunction "B_B") (pintype "passive"))
      (node (ref "R33") (pin "1") (pinfunction "1_1") (pintype "passive"))
    )
    (net (code "68") (name "Net-(Q18-PadC)") (class "Default")
      (node (ref "Q18") (pin "C") (pinfunction "C_C") (pintype "passive"))
      (node (ref "R32") (pin "2") (pinfunction "2_2") (pintype "passive"))
    )
    (net (code "69") (name "Net-(Q19-B)") (class "Default")
      (node (ref "Q19") (pin "1") (pinfunction "B_1") (pintype "passive"))
      (node (ref "R37") (pin "2") (pinfunction "2_2") (pintype "passive"))
    )
    (net (code "70") (name "Net-(Q19-C)") (class "Default")
      (node (ref "Q19") (pin "3") (pinfunction "C_3") (pintype "passive"))
      (node (ref "R36") (pin "2") (pinfunction "2_2") (pintype "passive"))
    )
    (net (code "71") (name "Net-(Q20-PadB)") (class "Default")
      (node (ref "Q20") (pin "B") (pinfunction "B_B") (pintype "passive"))
      (node (ref "R36") (pin "1") (pinfunction "1_1") (pintype "passive"))
    )
    (net (code "72") (name "Net-(Q20-PadC)") (class "Default")
      (node (ref "Q20") (pin "C") (pinfunction "C_C") (pintype "passive"))
      (node (ref "R35") (pin "2") (pinfunction "2_2") (pintype "passive"))
    )
    (net (code "73") (name "Net-(Q21-B)") (class "Default")
      (node (ref "Q21") (pin "1") (pinfunction "B_1") (pintype "passive"))
      (node (ref "R40") (pin "2") (pinfunction "2_2") (pintype "passive"))
    )
    (net (code "74") (name "Net-(Q21-C)") (class "Default")
      (node (ref "Q21") (pin "3") (pinfunction "C_3") (pintype "passive"))
      (node (ref "R39") (pin "2") (pinfunction "2_2") (pintype "passive"))
    )
    (net (code "75") (name "Net-(Q22-PadB)") (class "Default")
      (node (ref "Q22") (pin "B") (pinfunction "B_B") (pintype "passive"))
      (node (ref "R39") (pin "1") (pinfunction "1_1") (pintype "passive"))
    )
    (net (code "76") (name "Net-(Q22-PadC)") (class "Default")
      (node (ref "Q22") (pin "C") (pinfunction "C_C") (pintype "passive"))
      (node (ref "R38") (pin "2") (pinfunction "2_2") (pintype "passive"))
    )
    (net (code "77") (name "Net-(Q23-B)") (class "Default")
      (node (ref "Q23") (pin "1") (pinfunction "B_1") (pintype "passive"))
      (node (ref "R43") (pin "2") (pinfunction "2_2") (pintype "passive"))
    )
    (net (code "78") (name "Net-(Q23-C)") (class "Default")
      (node (ref "Q23") (pin "3") (pinfunction "C_3") (pintype "passive"))
      (node (ref "R42") (pin "2") (pinfunction "2_2") (pintype "passive"))
    )
    (net (code "79") (name "Net-(Q24-PadB)") (class "Default")
      (node (ref "Q24") (pin "B") (pinfunction "B_B") (pintype "passive"))
      (node (ref "R42") (pin "1") (pinfunction "1_1") (pintype "passive"))
    )
    (net (code "80") (name "Net-(Q24-PadC)") (class "Default")
      (node (ref "Q24") (pin "C") (pinfunction "C_C") (pintype "passive"))
      (node (ref "R41") (pin "2") (pinfunction "2_2") (pintype "passive"))
    )
    (net (code "81") (name "Net-(U$1-ANODE_B)") (class "Default")
      (node (ref "R23") (pin "1") (pinfunction "1_1") (pintype "passive"))
      (node (ref "U$1") (pin "AB") (pinfunction "ANODE_B_AB") (pintype "bidirectional"))
      (node (ref "U$3") (pin "AB") (pinfunction "ANODE_B_AB") (pintype "bidirectional"))
      (node (ref "U$5") (pin "AB") (pinfunction "ANODE_B_AB") (pintype "bidirectional"))
      (node (ref "U$6") (pin "AB") (pinfunction "ANODE_B_AB") (pintype "bidirectional"))
      (node (ref "U$7") (pin "AB") (pinfunction "ANODE_B_AB") (pintype "bidirectional"))
      (node (ref "U$8") (pin "AB") (pinfunction "ANODE_B_AB") (pintype "bidirectional"))
    )
    (net (code "82") (name "Net-(U$1-ANODE_G)") (class "Default")
      (node (ref "R25") (pin "1") (pinfunction "1_1") (pintype "passive"))
      (node (ref "U$1") (pin "AG") (pinfunction "ANODE_G_AG") (pintype "bidirectional"))
      (node (ref "U$3") (pin "AG") (pinfunction "ANODE_G_AG") (pintype "bidirectional"))
      (node (ref "U$5") (pin "AG") (pinfunction "ANODE_G_AG") (pintype "bidirectional"))
      (node (ref "U$6") (pin "AG") (pinfunction "ANODE_G_AG") (pintype "bidirectional"))
      (node (ref "U$7") (pin "AG") (pinfunction "ANODE_G_AG") (pintype "bidirectional"))
      (node (ref "U$8") (pin "AG") (pinfunction "ANODE_G_AG") (pintype "bidirectional"))
    )
    (net (code "83") (name "Net-(U$1-ANODE_R)") (class "Default")
      (node (ref "R24") (pin "1") (pinfunction "1_1") (pintype "passive"))
      (node (ref "U$1") (pin "AR") (pinfunction "ANODE_R_AR") (pintype "bidirectional"))
      (node (ref "U$3") (pin "AR") (pinfunction "ANODE_R_AR") (pintype "bidirectional"))
      (node (ref "U$5") (pin "AR") (pinfunction "ANODE_R_AR") (pintype "bidirectional"))
      (node (ref "U$6") (pin "AR") (pinfunction "ANODE_R_AR") (pintype "bidirectional"))
      (node (ref "U$7") (pin "AR") (pinfunction "ANODE_R_AR") (pintype "bidirectional"))
      (node (ref "U$8") (pin "AR") (pinfunction "ANODE_R_AR") (pintype "bidirectional"))
    )
    (net (code "84") (name "Net-(U2-PC0)") (class "Default")
      (node (ref "R21") (pin "1") (pinfunction "1_1") (pintype "passive"))
      (node (ref "U$2") (pin "SDA") (pinfunction "SDA_SDA") (pintype "bidirectional"))
      (node (ref "U2") (pin "10") (pinfunction "PC0_10") (pintype "bidirectional"))
    )
    (net (code "85") (name "Net-(U2-PC1)") (class "Default")
      (node (ref "R20") (pin "1") (pinfunction "1_1") (pintype "passive"))
      (node (ref "U$2") (pin "SCL") (pinfunction "SCL_SCL") (pintype "bidirectional"))
      (node (ref "U2") (pin "11") (pinfunction "PC1_11") (pintype "bidirectional"))
    )
    (net (code "86") (name "Net-(U2-PD0)") (class "Default")
      (node (ref "R19") (pin "1") (pinfunction "1_1") (pintype "passive"))
      (node (ref "U2") (pin "20") (pinfunction "PD0_20") (pintype "bidirectional"))
    )
    (net (code "87") (name "Net-(U2-PD1)") (class "Default")
      (node (ref "R18") (pin "1") (pinfunction "1_1") (pintype "passive"))
      (node (ref "U2") (pin "21") (pinfunction "PD1_21") (pintype "bidirectional"))
    )
    (net (code "88") (name "Net-(U2-PD2)") (class "Default")
      (node (ref "R17") (pin "1") (pinfunction "1_1") (pintype "passive"))
      (node (ref "U2") (pin "22") (pinfunction "PD2_22") (pintype "bidirectional"))
    )
    (net (code "89") (name "Net-(U2-PD3)") (class "Default")
      (node (ref "R22") (pin "1") (pinfunction "1_1") (pintype "passive"))
      (node (ref "U2") (pin "23") (pinfunction "PD3_23") (pintype "bidirectional"))
    )
    (net (code "90") (name "Net-(U2-PR0)") (class "Default")
      (node (ref "16MHZ") (pin "1") (pinfunction "1_1") (pintype "passive"))
      (node (ref "C1") (pin "2") (pinfunction "2_2") (pintype "passive"))
      (node (ref "U2") (pin "36") (pinfunction "PR0_36") (pintype "bidirectional"))
    )
    (net (code "91") (name "Net-(U2-PR1)") (class "Default")
      (node (ref "16MHZ") (pin "2") (pinfunction "2_2") (pintype "passive"))
      (node (ref "C2") (pin "2") (pinfunction "2_2") (pintype "passive"))
      (node (ref "U2") (pin "37") (pinfunction "PR1_37") (pintype "bidirectional"))
    )
    (net (code "92") (name "VCC") (class "Default")
      (node (ref "JP3") (pin "2") (pinfunction "2_2") (pintype "passive"))
      (node (ref "R20") (pin "2") (pinfunction "2_2") (pintype "passive"))
      (node (ref "R21") (pin "2") (pinfunction "2_2") (pintype "passive"))
      (node (ref "R23") (pin "2") (pinfunction "2_2") (pintype "passive"))
      (node (ref "R24") (pin "2") (pinfunction "2_2") (pintype "passive"))
      (node (ref "R25") (pin "2") (pinfunction "2_2") (pintype "passive"))
      (node (ref "U$2") (pin "VCC") (pinfunction "VCC_VCC") (pintype "power_in"))
      (node (ref "U2") (pin "9") (pinfunction "VCC_9") (pintype "power_in"))
      (node (ref "X1") (pin "5") (pinfunction "5_5") (pintype "passive"))
    )
    (net (code "93") (name "unconnected-(JP1-Pad1)") (class "Default")
      (node (ref "JP1") (pin "1") (pinfunction "1_1") (pintype "passive"))
    )
    (net (code "94") (name "unconnected-(JP1-Pad2)") (class "Default")
      (node (ref "JP1") (pin "2") (pinfunction "2_2") (pintype "passive"))
    )
    (net (code "95") (name "unconnected-(JP1-Pad3)") (class "Default")
      (node (ref "JP1") (pin "3") (pinfunction "3_3") (pintype "passive"))
    )
    (net (code "96") (name "unconnected-(JP1-Pad4)") (class "Default")
      (node (ref "JP1") (pin "4") (pinfunction "4_4") (pintype "passive"))
    )
    (net (code "97") (name "unconnected-(JP1-Pad5)") (class "Default")
      (node (ref "JP1") (pin "5") (pinfunction "5_5") (pintype "passive"))
    )
    (net (code "98") (name "unconnected-(JP1-Pad6)") (class "Default")
      (node (ref "JP1") (pin "6") (pinfunction "6_6") (pintype "passive"))
    )
    (net (code "99") (name "unconnected-(JP1-Pad7)") (class "Default")
      (node (ref "JP1") (pin "7") (pinfunction "7_7") (pintype "passive"))
    )
    (net (code "100") (name "unconnected-(JP1-Pad8)") (class "Default")
      (node (ref "JP1") (pin "8") (pinfunction "8_8") (pintype "passive"))
    )
    (net (code "101") (name "unconnected-(JP1-Pad9)") (class "Default")
      (node (ref "JP1") (pin "9") (pinfunction "9_9") (pintype "passive"))
    )
    (net (code "102") (name "unconnected-(JP1-Pad10)") (class "Default")
      (node (ref "JP1") (pin "10") (pinfunction "10_10") (pintype "passive"))
    )
    (net (code "103") (name "unconnected-(JP2-Pad1)") (class "Default")
      (node (ref "JP2") (pin "1") (pinfunction "1_1") (pintype "passive"))
    )
    (net (code "104") (name "unconnected-(JP2-Pad2)") (class "Default")
      (node (ref "JP2") (pin "2") (pinfunction "2_2") (pintype "passive"))
    )
    (net (code "105") (name "unconnected-(JP2-Pad3)") (class "Default")
      (node (ref "JP2") (pin "3") (pinfunction "3_3") (pintype "passive"))
    )
    (net (code "106") (name "unconnected-(JP2-Pad4)") (class "Default")
      (node (ref "JP2") (pin "4") (pinfunction "4_4") (pintype "passive"))
    )
    (net (code "107") (name "unconnected-(JP2-Pad5)") (class "Default")
      (node (ref "JP2") (pin "5") (pinfunction "5_5") (pintype "passive"))
    )
    (net (code "108") (name "unconnected-(JP2-Pad6)") (class "Default")
      (node (ref "JP2") (pin "6") (pinfunction "6_6") (pintype "passive"))
    )
    (net (code "109") (name "unconnected-(JP2-Pad7)") (class "Default")
      (node (ref "JP2") (pin "7") (pinfunction "7_7") (pintype "passive"))
    )
    (net (code "110") (name "unconnected-(JP2-Pad8)") (class "Default")
      (node (ref "JP2") (pin "8") (pinfunction "8_8") (pintype "passive"))
    )
    (net (code "111") (name "unconnected-(JP2-Pad9)") (class "Default")
      (node (ref "JP2") (pin "9") (pinfunction "9_9") (pintype "passive"))
    )
    (net (code "112") (name "unconnected-(JP2-Pad10)") (class "Default")
      (node (ref "JP2") (pin "10") (pinfunction "10_10") (pintype "passive"))
    )
    (net (code "113") (name "unconnected-(JP3-Pad3)") (class "Default")
      (node (ref "JP3") (pin "3") (pinfunction "3_3") (pintype "passive"))
    )
    (net (code "114") (name "unconnected-(JP3-Pad4)") (class "Default")
      (node (ref "JP3") (pin "4") (pinfunction "4_4") (pintype "passive"))
    )
    (net (code "115") (name "unconnected-(Q9-PadC)") (class "Default")
      (node (ref "Q9") (pin "C") (pinfunction "C_C") (pintype "passive"))
    )
    (net (code "116") (name "unconnected-(R9-Pad2)") (class "Default")
      (node (ref "R9") (pin "2") (pinfunction "2_2") (pintype "passive"))
    )
    (net (code "117") (name "unconnected-(R10-Pad2)") (class "Default")
      (node (ref "R10") (pin "2") (pinfunction "2_2") (pintype "passive"))
    )
    (net (code "118") (name "unconnected-(R11-Pad2)") (class "Default")
      (node (ref "R11") (pin "2") (pinfunction "2_2") (pintype "passive"))
    )
    (net (code "119") (name "unconnected-(R12-Pad2)") (class "Default")
      (node (ref "R12") (pin "2") (pinfunction "2_2") (pintype "passive"))
    )
    (net (code "120") (name "unconnected-(R13-Pad2)") (class "Default")
      (node (ref "R13") (pin "2") (pinfunction "2_2") (pintype "passive"))
    )
    (net (code "121") (name "unconnected-(R14-Pad2)") (class "Default")
      (node (ref "R14") (pin "2") (pinfunction "2_2") (pintype "passive"))
    )
    (net (code "122") (name "unconnected-(R15-Pad2)") (class "Default")
      (node (ref "R15") (pin "2") (pinfunction "2_2") (pintype "passive"))
    )
    (net (code "123") (name "unconnected-(R16-Pad2)") (class "Default")
      (node (ref "R16") (pin "2") (pinfunction "2_2") (pintype "passive"))
    )
    (net (code "124") (name "unconnected-(S1-P-Pad1)") (class "Default")
      (node (ref "S1") (pin "1") (pinfunction "P_1") (pintype "passive"))
    )
    (net (code "125") (name "unconnected-(S1-S-Pad2)") (class "Default")
      (node (ref "S1") (pin "2") (pinfunction "S_2") (pintype "passive"))
    )
    (net (code "126") (name "unconnected-(S2-P-Pad1)") (class "Default")
      (node (ref "S2") (pin "1") (pinfunction "P_1") (pintype "passive"))
    )
    (net (code "127") (name "unconnected-(S2-S-Pad2)") (class "Default")
      (node (ref "S2") (pin "2") (pinfunction "S_2") (pintype "passive"))
    )
    (net (code "128") (name "unconnected-(U$2-Pad32KHZ)") (class "Default")
      (node (ref "U$2") (pin "32KHZ") (pinfunction "32KHZ_32KHZ") (pintype "output"))
    )
    (net (code "129") (name "unconnected-(U$2-~{INT{slash}~SQW}-Pad!INT{slash}!!SQW)") (class "Default")
      (node (ref "U$2") (pin "!INT/!!SQW") (pinfunction "~{INT/~SQW}_!INT/!!SQW") (pintype "bidirectional"))
    )
    (net (code "130") (name "unconnected-(U$2-~{RST}-Pad!RST)") (class "Default")
      (node (ref "U$2") (pin "!RST") (pinfunction "~{RST}_!RST") (pintype "bidirectional"))
    )
    (net (code "131") (name "unconnected-(U$4-PadFIL_M)") (class "Default")
      (node (ref "U$4") (pin "FIL_M") (pinfunction "FIL_M_FIL_M") (pintype "bidirectional"))
    )
    (net (code "132") (name "unconnected-(U$4-PadGRID_P)") (class "Default")
      (node (ref "U$4") (pin "GRID_P") (pinfunction "GRID_P_GRID_P") (pintype "bidirectional"))
    )
    (net (code "133") (name "unconnected-(U$4-PadNC)") (class "Default")
      (node (ref "U$4") (pin "NC") (pinfunction "NC_NC") (pintype "bidirectional"))
    )
    (net (code "134") (name "unconnected-(U$9-PadFIL_M)") (class "Default")
      (node (ref "U$9") (pin "FIL_M") (pinfunction "FIL_M_FIL_M") (pintype "bidirectional"))
    )
    (net (code "135") (name "unconnected-(U$9-PadGRID_P)") (class "Default")
      (node (ref "U$9") (pin "GRID_P") (pinfunction "GRID_P_GRID_P") (pintype "bidirectional"))
    )
    (net (code "136") (name "unconnected-(U$9-PadNC)") (class "Default")
      (node (ref "U$9") (pin "NC") (pinfunction "NC_NC") (pintype "bidirectional"))
    )
    (net (code "137") (name "unconnected-(U$10-PadFIL_M)") (class "Default")
      (node (ref "U$10") (pin "FIL_M") (pinfunction "FIL_M_FIL_M") (pintype "bidirectional"))
    )
    (net (code "138") (name "unconnected-(U$10-PadGRID_P)") (class "Default")
      (node (ref "U$10") (pin "GRID_P") (pinfunction "GRID_P_GRID_P") (pintype "bidirectional"))
    )
    (net (code "139") (name "unconnected-(U$10-PadNC)") (class "Default")
      (node (ref "U$10") (pin "NC") (pinfunction "NC_NC") (pintype "bidirectional"))
    )
    (net (code "140") (name "unconnected-(U$11-PadFIL_M)") (class "Default")
      (node (ref "U$11") (pin "FIL_M") (pinfunction "FIL_M_FIL_M") (pintype "bidirectional"))
    )
    (net (code "141") (name "unconnected-(U$11-PadGRID_P)") (class "Default")
      (node (ref "U$11") (pin "GRID_P") (pinfunction "GRID_P_GRID_P") (pintype "bidirectional"))
    )
    (net (code "142") (name "unconnected-(U$11-PadNC)") (class "Default")
      (node (ref "U$11") (pin "NC") (pinfunction "NC_NC") (pintype "bidirectional"))
    )
    (net (code "143") (name "unconnected-(U$12-PadFIL_M)") (class "Default")
      (node (ref "U$12") (pin "FIL_M") (pinfunction "FIL_M_FIL_M") (pintype "bidirectional"))
    )
    (net (code "144") (name "unconnected-(U$12-PadGRID_P)") (class "Default")
      (node (ref "U$12") (pin "GRID_P") (pinfunction "GRID_P_GRID_P") (pintype "bidirectional"))
    )
    (net (code "145") (name "unconnected-(U$12-PadNC)") (class "Default")
      (node (ref "U$12") (pin "NC") (pinfunction "NC_NC") (pintype "bidirectional"))
    )
    (net (code "146") (name "unconnected-(U$13-PadFIL_M)") (class "Default")
      (node (ref "U$13") (pin "FIL_M") (pinfunction "FIL_M_FIL_M") (pintype "bidirectional"))
    )
    (net (code "147") (name "unconnected-(U$13-PadGRID_P)") (class "Default")
      (node (ref "U$13") (pin "GRID_P") (pinfunction "GRID_P_GRID_P") (pintype "bidirectional"))
    )
    (net (code "148") (name "unconnected-(U$13-PadNC)") (class "Default")
      (node (ref "U$13") (pin "NC") (pinfunction "NC_NC") (pintype "bidirectional"))
    )
    (net (code "149") (name "unconnected-(U2-GND-Pad30)") (class "Default")
      (node (ref "U2") (pin "30") (pinfunction "GND_30") (pintype "passive"))
    )
    (net (code "150") (name "unconnected-(U2-GND_2-Pad8)") (class "Default")
      (node (ref "U2") (pin "8") (pinfunction "GND_2_8") (pintype "passive"))
    )
    (net (code "151") (name "unconnected-(U2-GND_3-Pad38)") (class "Default")
      (node (ref "U2") (pin "38") (pinfunction "GND_3_38") (pintype "passive"))
    )
    (net (code "152") (name "unconnected-(U2-GND_4-Pad18)") (class "Default")
      (node (ref "U2") (pin "18") (pinfunction "GND_4_18") (pintype "passive"))
    )
    (net (code "153") (name "unconnected-(U2-PB0-Pad4)") (class "Default")
      (node (ref "U2") (pin "4") (pinfunction "PB0_4") (pintype "bidirectional"))
    )
    (net (code "154") (name "unconnected-(U2-PB1-Pad5)") (class "Default")
      (node (ref "U2") (pin "5") (pinfunction "PB1_5") (pintype "bidirectional"))
    )
    (net (code "155") (name "unconnected-(U2-PB2-Pad6)") (class "Default")
      (node (ref "U2") (pin "6") (pinfunction "PB2_6") (pintype "bidirectional"))
    )
    (net (code "156") (name "unconnected-(U2-PB3-Pad7)") (class "Default")
      (node (ref "U2") (pin "7") (pinfunction "PB3_7") (pintype "bidirectional"))
    )
    (net (code "157") (name "unconnected-(U2-PC4-Pad14)") (class "Default")
      (node (ref "U2") (pin "14") (pinfunction "PC4_14") (pintype "bidirectional"))
    )
    (net (code "158") (name "unconnected-(U2-PC5-Pad15)") (class "Default")
      (node (ref "U2") (pin "15") (pinfunction "PC5_15") (pintype "bidirectional"))
    )
    (net (code "159") (name "unconnected-(U2-PC6-Pad16)") (class "Default")
      (node (ref "U2") (pin "16") (pinfunction "PC6_16") (pintype "bidirectional"))
    )
    (net (code "160") (name "unconnected-(U2-PC7-Pad17)") (class "Default")
      (node (ref "U2") (pin "17") (pinfunction "PC7_17") (pintype "bidirectional"))
    )
    (net (code "161") (name "unconnected-(U2-PE2-Pad32)") (class "Default")
      (node (ref "U2") (pin "32") (pinfunction "PE2_32") (pintype "bidirectional"))
    )
    (net (code "162") (name "unconnected-(U2-PE3-Pad33)") (class "Default")
      (node (ref "U2") (pin "33") (pinfunction "PE3_33") (pintype "bidirectional"))
    )
  )
)
